# receiver.net
KiCad netlist of a schematic drawn in EAGLE
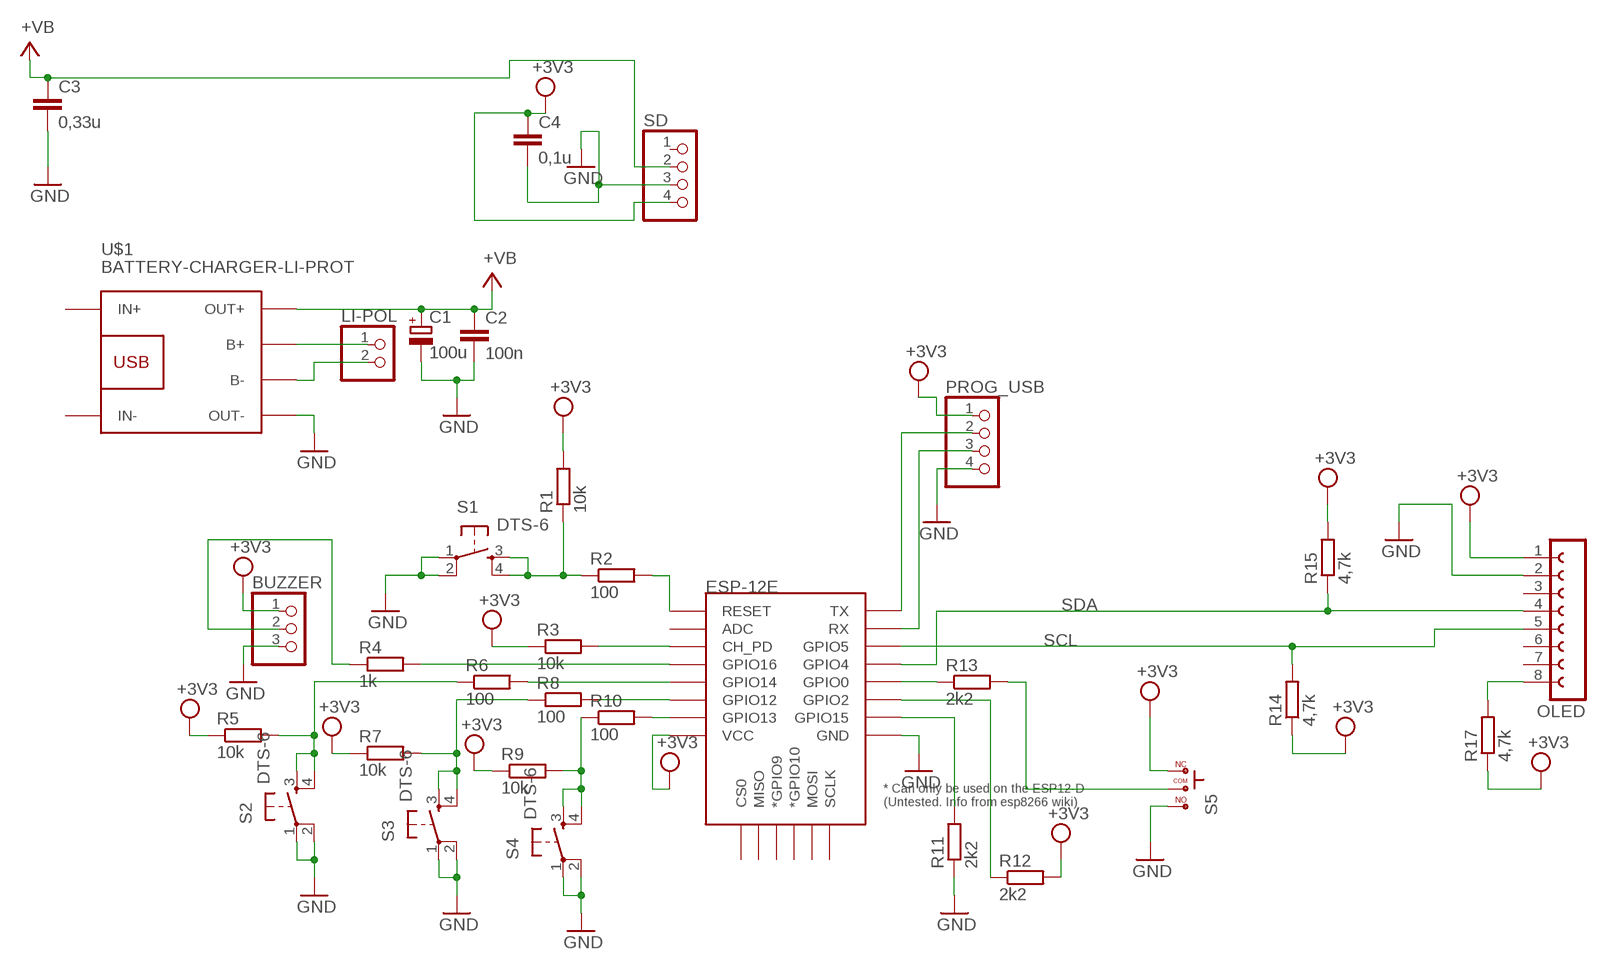
[diagram p0: schematic, sheet 1]

(export (version "E")
  (design (tool "Eeschema 10.0.6"))
  (components
    (comp (ref "BUZZER")
      (value "PINHD-1X3/90")
      (footprint "eagle-import:1X03_90")
      (libsource (lib "eagle-import") (part "PINHD-1X3/90"))
    )
    (comp (ref "C1")
      (value "100u")
      (footprint "eagle-import:E2,5-6")
      (libsource (lib "eagle-import") (part "CPOL-EUE2.5-6"))
    )
    (comp (ref "C2")
      (value "100n")
      (footprint "eagle-import:C025-025X050")
      (libsource (lib "eagle-import") (part "C-EU025-025X050"))
    )
    (comp (ref "C3")
      (value "0,33u")
      (footprint "eagle-import:C025-025X050")
      (libsource (lib "eagle-import") (part "C-EU025-025X050"))
    )
    (comp (ref "C4")
      (value "0,1u")
      (footprint "eagle-import:C025-025X050")
      (libsource (lib "eagle-import") (part "C-EU025-025X050"))
    )
    (comp (ref "ESP-12E")
      (value "ESP12ESMD")
      (footprint "eagle-import:ESP12E-SMD")
      (libsource (lib "eagle-import") (part "ESP12ESMD"))
    )
    (comp (ref "LI-POL")
      (value "PINHD-1X2")
      (footprint "eagle-import:1X02")
      (libsource (lib "eagle-import") (part "PINHD-1X2"))
    )
    (comp (ref "OLED")
      (value "FE08-1")
      (footprint "eagle-import:FE08")
      (libsource (lib "eagle-import") (part "FE08-1"))
    )
    (comp (ref "PROG_USB")
      (value "PINHD-1X4")
      (footprint "eagle-import:1X04")
      (libsource (lib "eagle-import") (part "PINHD-1X4"))
    )
    (comp (ref "R1")
      (value "10k")
      (footprint "eagle-import:0204_7")
      (libsource (lib "eagle-import") (part "R-EU_0204/7"))
    )
    (comp (ref "R2")
      (value "100")
      (footprint "eagle-import:0204_7")
      (libsource (lib "eagle-import") (part "R-EU_0204/7"))
    )
    (comp (ref "R3")
      (value "10k")
      (footprint "eagle-import:0204_7")
      (libsource (lib "eagle-import") (part "R-EU_0204/7"))
    )
    (comp (ref "R4")
      (value "1k")
      (footprint "eagle-import:0204_7")
      (libsource (lib "eagle-import") (part "R-EU_0204/7"))
    )
    (comp (ref "R5")
      (value "10k")
      (footprint "eagle-import:0204_7")
      (libsource (lib "eagle-import") (part "R-EU_0204/7"))
    )
    (comp (ref "R6")
      (value "100")
      (footprint "eagle-import:0204_7")
      (libsource (lib "eagle-import") (part "R-EU_0204/7"))
    )
    (comp (ref "R7")
      (value "10k")
      (footprint "eagle-import:0204_7")
      (libsource (lib "eagle-import") (part "R-EU_0204/7"))
    )
    (comp (ref "R8")
      (value "100")
      (footprint "eagle-import:0204_7")
      (libsource (lib "eagle-import") (part "R-EU_0204/7"))
    )
    (comp (ref "R9")
      (value "10k")
      (footprint "eagle-import:0204_7")
      (libsource (lib "eagle-import") (part "R-EU_0204/7"))
    )
    (comp (ref "R10")
      (value "100")
      (footprint "eagle-import:0204_7")
      (libsource (lib "eagle-import") (part "R-EU_0204/7"))
    )
    (comp (ref "R11")
      (value "2k2")
      (footprint "eagle-import:0204_7")
      (libsource (lib "eagle-import") (part "R-EU_0204/7"))
    )
    (comp (ref "R12")
      (value "2k2")
      (footprint "eagle-import:0204_7")
      (libsource (lib "eagle-import") (part "R-EU_0204/7"))
    )
    (comp (ref "R13")
      (value "2k2")
      (footprint "eagle-import:0204_7")
      (libsource (lib "eagle-import") (part "R-EU_0204/7"))
    )
    (comp (ref "R14")
      (value "4,7k")
      (footprint "eagle-import:0204_7")
      (libsource (lib "eagle-import") (part "R-EU_0204/7"))
    )
    (comp (ref "R15")
      (value "4,7k")
      (footprint "eagle-import:0204_7")
      (libsource (lib "eagle-import") (part "R-EU_0204/7"))
    )
    (comp (ref "R17")
      (value "4,7k")
      (footprint "eagle-import:0204_7")
      (libsource (lib "eagle-import") (part "R-EU_0204/7"))
    )
    (comp (ref "S1")
      (value "DTS-6")
      (footprint "eagle-import:DTS-6")
      (libsource (lib "eagle-import") (part "DTS-6"))
    )
    (comp (ref "S2")
      (value "DTS-6")
      (footprint "eagle-import:DTS-6")
      (libsource (lib "eagle-import") (part "DTS-6"))
    )
    (comp (ref "S3")
      (value "DTS-6")
      (footprint "eagle-import:DTS-6")
      (libsource (lib "eagle-import") (part "DTS-6"))
    )
    (comp (ref "S4")
      (value "DTS-6")
      (footprint "eagle-import:DTS-6")
      (libsource (lib "eagle-import") (part "DTS-6"))
    )
    (comp (ref "S5")
      (value "-SWITCH")
      (footprint "eagle-import:CON3")
      (libsource (lib "eagle-import") (part "-SWITCH"))
    )
    (comp (ref "SD")
      (value "PINHD-1X4")
      (footprint "eagle-import:1X04")
      (libsource (lib "eagle-import") (part "PINHD-1X4"))
    )
    (comp (ref "U$1")
      (value "BATTERY-CHARGER-LI-PROT")
      (footprint "eagle-import:BATTERY-CHARGER-LI-PROT")
      (libsource (lib "eagle-import") (part "BATTERY-CHARGER-LI-PROT"))
    )
  )
  (nets
    (net (code "1") (name "+3V3") (class "Default")
      (node (ref "BUZZER") (pin "1") (pinfunction "1_1") (pintype "passive"))
      (node (ref "C4") (pin "1") (pinfunction "1_1") (pintype "passive"))
      (node (ref "ESP-12E") (pin "VCC") (pinfunction "VCC_VCC") (pintype "bidirectional"))
      (node (ref "OLED") (pin "1") (pinfunction "1_1") (pintype "passive"))
      (node (ref "PROG_USB") (pin "1") (pinfunction "1_1") (pintype "passive"))
      (node (ref "R1") (pin "2") (pinfunction "2_2") (pintype "passive"))
      (node (ref "R12") (pin "2") (pinfunction "2_2") (pintype "passive"))
      (node (ref "R14") (pin "1") (pinfunction "1_1") (pintype "passive"))
      (node (ref "R15") (pin "2") (pinfunction "2_2") (pintype "passive"))
      (node (ref "R17") (pin "1") (pinfunction "1_1") (pintype "passive"))
      (node (ref "R3") (pin "1") (pinfunction "1_1") (pintype "passive"))
      (node (ref "R5") (pin "1") (pinfunction "1_1") (pintype "passive"))
      (node (ref "R7") (pin "1") (pinfunction "1_1") (pintype "passive"))
      (node (ref "R9") (pin "1") (pinfunction "1_1") (pintype "passive"))
      (node (ref "S5") (pin "P$1") (pinfunction "1_P$1") (pintype "passive"))
      (node (ref "SD") (pin "4") (pinfunction "4_4") (pintype "passive"))
    )
    (net (code "2") (name "+VB") (class "Default")
      (node (ref "C1") (pin "+") (pinfunction "+_+") (pintype "passive"))
      (node (ref "C2") (pin "1") (pinfunction "1_1") (pintype "passive"))
      (node (ref "C3") (pin "1") (pinfunction "1_1") (pintype "passive"))
      (node (ref "SD") (pin "2") (pinfunction "2_2") (pintype "passive"))
      (node (ref "U$1") (pin "OUT+") (pinfunction "OUT+_OUT+") (pintype "bidirectional"))
    )
    (net (code "3") (name "/SCL") (class "Default")
      (node (ref "ESP-12E") (pin "GPIO5") (pinfunction "GPIO5_GPIO5") (pintype "bidirectional"))
      (node (ref "OLED") (pin "5") (pinfunction "5_5") (pintype "passive"))
      (node (ref "R14") (pin "2") (pinfunction "2_2") (pintype "passive"))
    )
    (net (code "4") (name "/SDA") (class "Default")
      (node (ref "ESP-12E") (pin "GPIO4") (pinfunction "GPIO4_GPIO4") (pintype "bidirectional"))
      (node (ref "OLED") (pin "4") (pinfunction "4_4") (pintype "passive"))
      (node (ref "R15") (pin "1") (pinfunction "1_1") (pintype "passive"))
    )
    (net (code "5") (name "GND") (class "Default")
      (node (ref "BUZZER") (pin "3") (pinfunction "3_3") (pintype "passive"))
      (node (ref "C1") (pin "-") (pinfunction "-_-") (pintype "passive"))
      (node (ref "C2") (pin "2") (pinfunction "2_2") (pintype "passive"))
      (node (ref "C3") (pin "2") (pinfunction "2_2") (pintype "passive"))
      (node (ref "C4") (pin "2") (pinfunction "2_2") (pintype "passive"))
      (node (ref "ESP-12E") (pin "GND") (pinfunction "GND_GND") (pintype "bidirectional"))
      (node (ref "OLED") (pin "2") (pinfunction "2_2") (pintype "passive"))
      (node (ref "PROG_USB") (pin "4") (pinfunction "4_4") (pintype "passive"))
      (node (ref "R11") (pin "1") (pinfunction "1_1") (pintype "passive"))
      (node (ref "S1") (pin "1") (pinfunction "1_1") (pintype "passive"))
      (node (ref "S1") (pin "2") (pinfunction "2_2") (pintype "passive"))
      (node (ref "S2") (pin "1") (pinfunction "1_1") (pintype "passive"))
      (node (ref "S2") (pin "2") (pinfunction "2_2") (pintype "passive"))
      (node (ref "S3") (pin "1") (pinfunction "1_1") (pintype "passive"))
      (node (ref "S3") (pin "2") (pinfunction "2_2") (pintype "passive"))
      (node (ref "S4") (pin "1") (pinfunction "1_1") (pintype "passive"))
      (node (ref "S4") (pin "2") (pinfunction "2_2") (pintype "passive"))
      (node (ref "S5") (pin "P$3") (pinfunction "3_P$3") (pintype "passive"))
      (node (ref "SD") (pin "3") (pinfunction "3_3") (pintype "passive"))
      (node (ref "U$1") (pin "OUT-") (pinfunction "OUT-_OUT-") (pintype "bidirectional"))
    )
    (net (code "6") (name "Net-(BUZZER-Pad2)") (class "Default")
      (node (ref "BUZZER") (pin "2") (pinfunction "2_2") (pintype "passive"))
      (node (ref "R4") (pin "1") (pinfunction "1_1") (pintype "passive"))
    )
    (net (code "7") (name "Net-(ESP-12E-PadCH_PD)") (class "Default")
      (node (ref "ESP-12E") (pin "CH_PD") (pinfunction "CH_PD_CH_PD") (pintype "bidirectional"))
      (node (ref "R3") (pin "2") (pinfunction "2_2") (pintype "passive"))
    )
    (net (code "8") (name "Net-(ESP-12E-PadGPIO0)") (class "Default")
      (node (ref "ESP-12E") (pin "GPIO0") (pinfunction "GPIO0_GPIO0") (pintype "bidirectional"))
      (node (ref "R13") (pin "1") (pinfunction "1_1") (pintype "passive"))
    )
    (net (code "9") (name "Net-(ESP-12E-PadGPIO2)") (class "Default")
      (node (ref "ESP-12E") (pin "GPIO2") (pinfunction "GPIO2_GPIO2") (pintype "bidirectional"))
      (node (ref "R12") (pin "1") (pinfunction "1_1") (pintype "passive"))
    )
    (net (code "10") (name "Net-(ESP-12E-PadGPIO12)") (class "Default")
      (node (ref "ESP-12E") (pin "GPIO12") (pinfunction "GPIO12_GPIO12") (pintype "bidirectional"))
      (node (ref "R8") (pin "2") (pinfunction "2_2") (pintype "passive"))
    )
    (net (code "11") (name "Net-(ESP-12E-PadGPIO13)") (class "Default")
      (node (ref "ESP-12E") (pin "GPIO13") (pinfunction "GPIO13_GPIO13") (pintype "bidirectional"))
      (node (ref "R10") (pin "2") (pinfunction "2_2") (pintype "passive"))
    )
    (net (code "12") (name "Net-(ESP-12E-PadGPIO14)") (class "Default")
      (node (ref "ESP-12E") (pin "GPIO14") (pinfunction "GPIO14_GPIO14") (pintype "bidirectional"))
      (node (ref "R6") (pin "2") (pinfunction "2_2") (pintype "passive"))
    )
    (net (code "13") (name "Net-(ESP-12E-PadGPIO15)") (class "Default")
      (node (ref "ESP-12E") (pin "GPIO15") (pinfunction "GPIO15_GPIO15") (pintype "bidirectional"))
      (node (ref "R11") (pin "2") (pinfunction "2_2") (pintype "passive"))
    )
    (net (code "14") (name "Net-(ESP-12E-PadGPIO16)") (class "Default")
      (node (ref "ESP-12E") (pin "GPIO16") (pinfunction "GPIO16_GPIO16") (pintype "bidirectional"))
      (node (ref "R4") (pin "2") (pinfunction "2_2") (pintype "passive"))
    )
    (net (code "15") (name "Net-(ESP-12E-PadRESET)") (class "Default")
      (node (ref "ESP-12E") (pin "RESET") (pinfunction "RESET_RESET") (pintype "bidirectional"))
      (node (ref "R2") (pin "2") (pinfunction "2_2") (pintype "passive"))
    )
    (net (code "16") (name "Net-(ESP-12E-RX)") (class "Default")
      (node (ref "ESP-12E") (pin "RXD0") (pinfunction "RX_RXD0") (pintype "bidirectional"))
      (node (ref "PROG_USB") (pin "3") (pinfunction "3_3") (pintype "passive"))
    )
    (net (code "17") (name "Net-(ESP-12E-TX)") (class "Default")
      (node (ref "ESP-12E") (pin "TXD0") (pinfunction "TX_TXD0") (pintype "bidirectional"))
      (node (ref "PROG_USB") (pin "2") (pinfunction "2_2") (pintype "passive"))
    )
    (net (code "18") (name "Net-(LI-POL-Pad1)") (class "Default")
      (node (ref "LI-POL") (pin "1") (pinfunction "1_1") (pintype "passive"))
      (node (ref "U$1") (pin "B+") (pinfunction "B+_B+") (pintype "bidirectional"))
    )
    (net (code "19") (name "Net-(LI-POL-Pad2)") (class "Default")
      (node (ref "LI-POL") (pin "2") (pinfunction "2_2") (pintype "passive"))
      (node (ref "U$1") (pin "B-") (pinfunction "B-_B-") (pintype "bidirectional"))
    )
    (net (code "20") (name "Net-(OLED-Pad8)") (class "Default")
      (node (ref "OLED") (pin "8") (pinfunction "8_8") (pintype "passive"))
      (node (ref "R17") (pin "2") (pinfunction "2_2") (pintype "passive"))
    )
    (net (code "21") (name "Net-(R1-Pad1)") (class "Default")
      (node (ref "R1") (pin "1") (pinfunction "1_1") (pintype "passive"))
      (node (ref "R2") (pin "1") (pinfunction "1_1") (pintype "passive"))
      (node (ref "S1") (pin "3") (pinfunction "3_3") (pintype "passive"))
      (node (ref "S1") (pin "4") (pinfunction "4_4") (pintype "passive"))
    )
    (net (code "22") (name "Net-(R5-Pad2)") (class "Default")
      (node (ref "R5") (pin "2") (pinfunction "2_2") (pintype "passive"))
      (node (ref "R6") (pin "1") (pinfunction "1_1") (pintype "passive"))
      (node (ref "S2") (pin "3") (pinfunction "3_3") (pintype "passive"))
      (node (ref "S2") (pin "4") (pinfunction "4_4") (pintype "passive"))
    )
    (net (code "23") (name "Net-(R7-Pad2)") (class "Default")
      (node (ref "R7") (pin "2") (pinfunction "2_2") (pintype "passive"))
      (node (ref "R8") (pin "1") (pinfunction "1_1") (pintype "passive"))
      (node (ref "S3") (pin "3") (pinfunction "3_3") (pintype "passive"))
      (node (ref "S3") (pin "4") (pinfunction "4_4") (pintype "passive"))
    )
    (net (code "24") (name "Net-(R10-Pad1)") (class "Default")
      (node (ref "R10") (pin "1") (pinfunction "1_1") (pintype "passive"))
      (node (ref "R9") (pin "2") (pinfunction "2_2") (pintype "passive"))
      (node (ref "S4") (pin "3") (pinfunction "3_3") (pintype "passive"))
      (node (ref "S4") (pin "4") (pinfunction "4_4") (pintype "passive"))
    )
    (net (code "25") (name "Net-(S5-2)") (class "Default")
      (node (ref "R13") (pin "2") (pinfunction "2_2") (pintype "passive"))
      (node (ref "S5") (pin "P$2") (pinfunction "2_P$2") (pintype "passive"))
    )
    (net (code "26") (name "unconnected-(ESP-12E-*GPIO9-PadGPIO9)") (class "Default")
      (node (ref "ESP-12E") (pin "GPIO9") (pinfunction "*GPIO9_GPIO9") (pintype "bidirectional"))
    )
    (net (code "27") (name "unconnected-(ESP-12E-*GPIO10-PadGPIO10)") (class "Default")
      (node (ref "ESP-12E") (pin "GPIO10") (pinfunction "*GPIO10_GPIO10") (pintype "bidirectional"))
    )
    (net (code "28") (name "unconnected-(ESP-12E-PadADC)") (class "Default")
      (node (ref "ESP-12E") (pin "ADC") (pinfunction "ADC_ADC") (pintype "bidirectional"))
    )
    (net (code "29") (name "unconnected-(ESP-12E-PadCS0)") (class "Default")
      (node (ref "ESP-12E") (pin "CS0") (pinfunction "CS0_CS0") (pintype "bidirectional"))
    )
    (net (code "30") (name "unconnected-(ESP-12E-PadMISO)") (class "Default")
      (node (ref "ESP-12E") (pin "MISO") (pinfunction "MISO_MISO") (pintype "bidirectional"))
    )
    (net (code "31") (name "unconnected-(ESP-12E-PadMOSI)") (class "Default")
      (node (ref "ESP-12E") (pin "MOSI") (pinfunction "MOSI_MOSI") (pintype "bidirectional"))
    )
    (net (code "32") (name "unconnected-(ESP-12E-PadSCLK)") (class "Default")
      (node (ref "ESP-12E") (pin "SCLK") (pinfunction "SCLK_SCLK") (pintype "bidirectional"))
    )
    (net (code "33") (name "unconnected-(OLED-Pad3)") (class "Default")
      (node (ref "OLED") (pin "3") (pinfunction "3_3") (pintype "passive"))
    )
    (net (code "34") (name "unconnected-(OLED-Pad6)") (class "Default")
      (node (ref "OLED") (pin "6") (pinfunction "6_6") (pintype "passive"))
    )
    (net (code "35") (name "unconnected-(OLED-Pad7)") (class "Default")
      (node (ref "OLED") (pin "7") (pinfunction "7_7") (pintype "passive"))
    )
    (net (code "36") (name "unconnected-(SD-Pad1)") (class "Default")
      (node (ref "SD") (pin "1") (pinfunction "1_1") (pintype "passive"))
    )
    (net (code "37") (name "unconnected-(U$1-PadIN+)") (class "Default")
      (node (ref "U$1") (pin "IN+") (pinfunction "IN+_IN+") (pintype "bidirectional"))
    )
    (net (code "38") (name "unconnected-(U$1-PadIN-)") (class "Default")
      (node (ref "U$1") (pin "IN-") (pinfunction "IN-_IN-") (pintype "bidirectional"))
    )
  )
)
